# MCU.net
KiCad netlist of a schematic drawn in Altium Designer
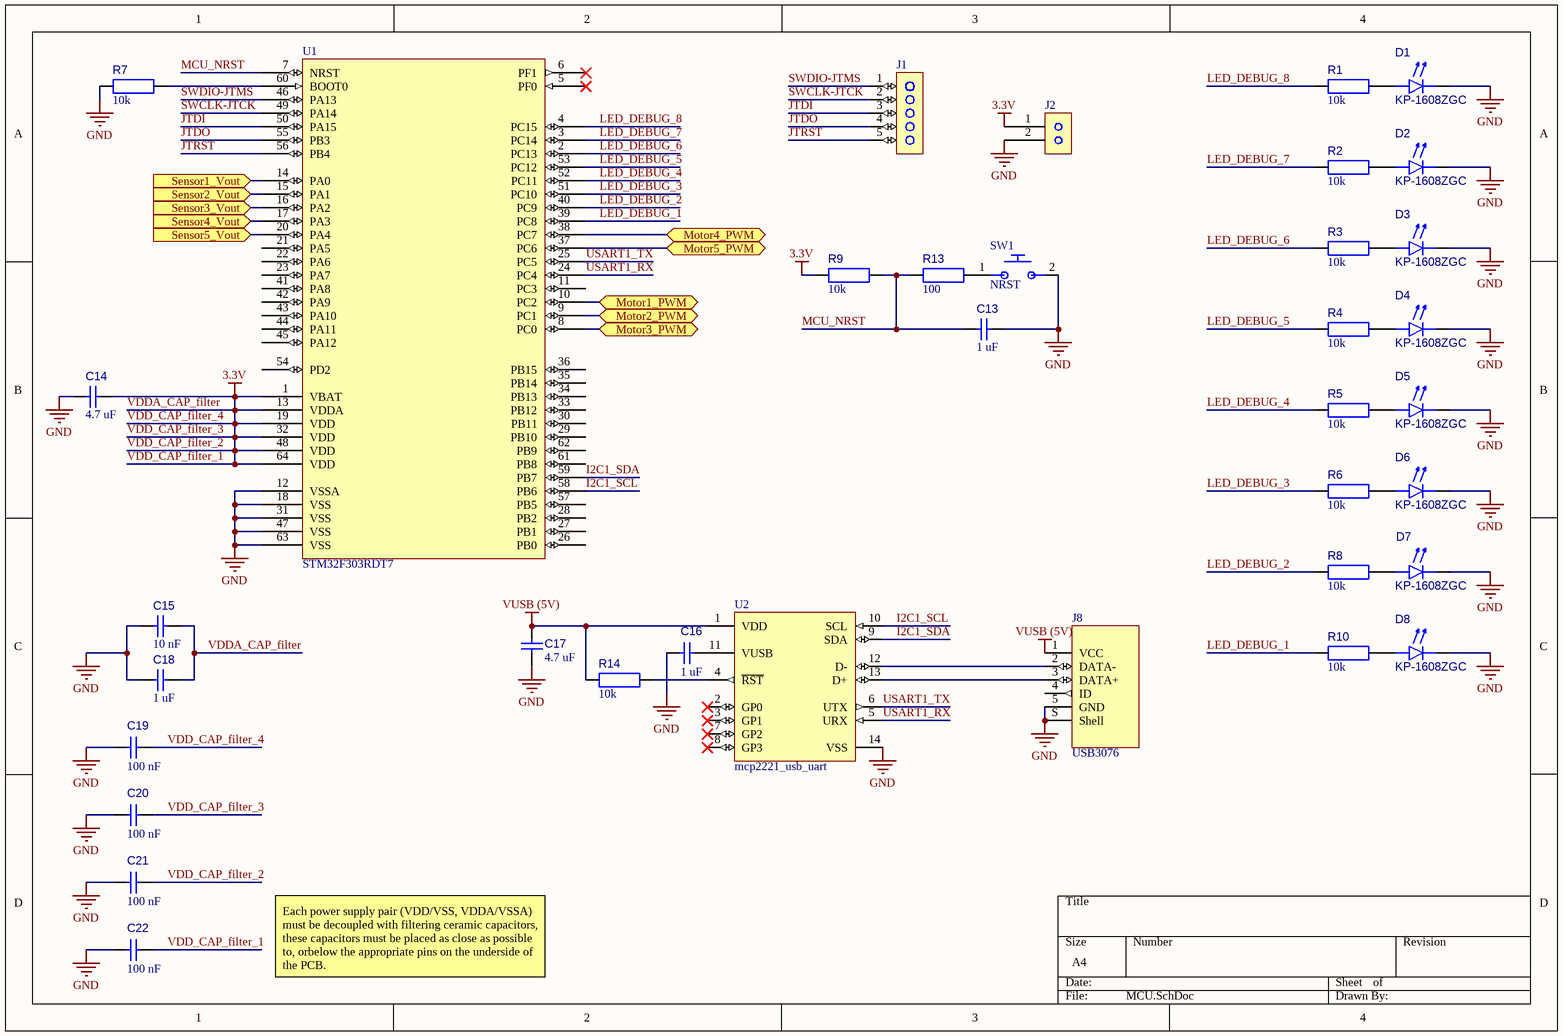
[diagram p0: MCU.SchDoc]

(export (version "E")
  (design (tool "Eeschema 10.0.6"))
  (components
    (comp (ref "C13")
      (value "Capacitor 0603 generic")
      (footprint "CAPC1608X08N")
      (description "Generic 0603 capacitor. No set voltage/capacitance rating.")
      (fields (field (name "CAPACITANCE") "1 uF"))
      (libsource (lib "Martin Kaur") (part "CAP-0603"))
    )
    (comp (ref "C14")
      (value "Capacitor 0603 generic")
      (footprint "CAPC1608X08N")
      (description "Generic 0603 capacitor. No set voltage/capacitance rating.")
      (fields (field (name "CAPACITANCE") "4.7 uF"))
      (libsource (lib "Martin Kaur") (part "CAP-0603"))
    )
    (comp (ref "C15")
      (value "Capacitor 0603 generic")
      (footprint "CAPC1608X08N")
      (description "Generic 0603 capacitor. No set voltage/capacitance rating.")
      (fields (field (name "CAPACITANCE") "10 nF"))
      (libsource (lib "Martin Kaur") (part "CAP-0603"))
    )
    (comp (ref "C16")
      (value "Capacitor 0603 generic")
      (footprint "CAPC1608X08N")
      (description "Generic 0603 capacitor. No set voltage/capacitance rating.")
      (fields (field (name "CAPACITANCE") "1 uF"))
      (libsource (lib "Martin Kaur") (part "CAP-0603"))
    )
    (comp (ref "C17")
      (value "Capacitor 0603 generic")
      (footprint "CAPC1608X08N")
      (description "Generic 0603 capacitor. No set voltage/capacitance rating.")
      (fields (field (name "CAPACITANCE") "4.7 uF"))
      (libsource (lib "Martin Kaur") (part "CAP-0603"))
    )
    (comp (ref "C18")
      (value "Capacitor 0603 generic")
      (footprint "CAPC1608X08N")
      (description "Generic 0603 capacitor. No set voltage/capacitance rating.")
      (fields (field (name "CAPACITANCE") "1 uF"))
      (libsource (lib "Martin Kaur") (part "CAP-0603"))
    )
    (comp (ref "C19")
      (value "Capacitor 0603 generic")
      (footprint "CAPC1608X08N")
      (description "Generic 0603 capacitor. No set voltage/capacitance rating.")
      (fields (field (name "CAPACITANCE") "100 nF"))
      (libsource (lib "Martin Kaur") (part "CAP-0603"))
    )
    (comp (ref "C20")
      (value "Capacitor 0603 generic")
      (footprint "CAPC1608X08N")
      (description "Generic 0603 capacitor. No set voltage/capacitance rating.")
      (fields (field (name "CAPACITANCE") "100 nF"))
      (libsource (lib "Martin Kaur") (part "CAP-0603"))
    )
    (comp (ref "C21")
      (value "Capacitor 0603 generic")
      (footprint "CAPC1608X08N")
      (description "Generic 0603 capacitor. No set voltage/capacitance rating.")
      (fields (field (name "CAPACITANCE") "100 nF"))
      (libsource (lib "Martin Kaur") (part "CAP-0603"))
    )
    (comp (ref "C22")
      (value "Capacitor 0603 generic")
      (footprint "CAPC1608X08N")
      (description "Generic 0603 capacitor. No set voltage/capacitance rating.")
      (fields (field (name "CAPACITANCE") "100 nF"))
      (libsource (lib "Martin Kaur") (part "CAP-0603"))
    )
    (comp (ref "D1")
      (value "KP-1608ZGC")
      (footprint "DIOM1608X11N")
      (description "Single Color LED, Green, Water Clear, 1.2mm")
      (libsource (lib "Martin Kaur") (part "KP-1608ZGC"))
    )
    (comp (ref "D2")
      (value "KP-1608ZGC")
      (footprint "DIOM1608X11N")
      (description "Single Color LED, Green, Water Clear, 1.2mm")
      (libsource (lib "Martin Kaur") (part "KP-1608ZGC"))
    )
    (comp (ref "D3")
      (value "KP-1608ZGC")
      (footprint "DIOM1608X11N")
      (description "Single Color LED, Green, Water Clear, 1.2mm")
      (libsource (lib "Martin Kaur") (part "KP-1608ZGC"))
    )
    (comp (ref "D4")
      (value "KP-1608ZGC")
      (footprint "DIOM1608X11N")
      (description "Single Color LED, Green, Water Clear, 1.2mm")
      (libsource (lib "Martin Kaur") (part "KP-1608ZGC"))
    )
    (comp (ref "D5")
      (value "KP-1608ZGC")
      (footprint "DIOM1608X11N")
      (description "Single Color LED, Green, Water Clear, 1.2mm")
      (libsource (lib "Martin Kaur") (part "KP-1608ZGC"))
    )
    (comp (ref "D6")
      (value "KP-1608ZGC")
      (footprint "DIOM1608X11N")
      (description "Single Color LED, Green, Water Clear, 1.2mm")
      (libsource (lib "Martin Kaur") (part "KP-1608ZGC"))
    )
    (comp (ref "D7")
      (value "KP-1608ZGC")
      (footprint "DIOM1608X11N")
      (description "Single Color LED, Green, Water Clear, 1.2mm")
      (libsource (lib "Martin Kaur") (part "KP-1608ZGC"))
    )
    (comp (ref "D8")
      (value "KP-1608ZGC")
      (footprint "DIOM1608X11N")
      (description "Single Color LED, Green, Water Clear, 1.2mm")
      (libsource (lib "Martin Kaur") (part "KP-1608ZGC"))
    )
    (comp (ref "J1")
      (value "Header-2.54-ZL201-05G")
      (footprint "Header-2.54-ZL201-05G-Footprint-1")
      (description "Male header, pitch 2.54 mm, 1x5 pins")
      (libsource (lib "Martin Kaur") (part "Header-2.54-ZL201-05G"))
    )
    (comp (ref "J2")
      (value "2_pin_f_2_54")
      (footprint "2_pin_f_2_54-Footprint-1")
      (description "2 pin female header, 2.54 mm pitch.")
      (libsource (lib "Martin Kaur") (part "2_pin_header"))
    )
    (comp (ref "J8")
      (value "USB3076")
      (footprint "USB3076-XX-X_revC")
      (libsource (lib "Martin Kaur") (part "USB3076-XX-X_revC"))
    )
    (comp (ref "R1")
      (value "Resistor 0603 generic")
      (footprint "RESC1608X04N")
      (description "Generic 0603 resistor, no fixed value.")
      (fields (field (name "RESISTANCE") "10k"))
      (libsource (lib "Martin Kaur") (part "RES0603"))
    )
    (comp (ref "R2")
      (value "Resistor 0603 generic")
      (footprint "RESC1608X04N")
      (description "Generic 0603 resistor, no fixed value.")
      (fields (field (name "RESISTANCE") "10k"))
      (libsource (lib "Martin Kaur") (part "RES0603"))
    )
    (comp (ref "R3")
      (value "Resistor 0603 generic")
      (footprint "RESC1608X04N")
      (description "Generic 0603 resistor, no fixed value.")
      (fields (field (name "RESISTANCE") "10k"))
      (libsource (lib "Martin Kaur") (part "RES0603"))
    )
    (comp (ref "R4")
      (value "Resistor 0603 generic")
      (footprint "RESC1608X04N")
      (description "Generic 0603 resistor, no fixed value.")
      (fields (field (name "RESISTANCE") "10k"))
      (libsource (lib "Martin Kaur") (part "RES0603"))
    )
    (comp (ref "R5")
      (value "Resistor 0603 generic")
      (footprint "RESC1608X04N")
      (description "Generic 0603 resistor, no fixed value.")
      (fields (field (name "RESISTANCE") "10k"))
      (libsource (lib "Martin Kaur") (part "RES0603"))
    )
    (comp (ref "R6")
      (value "Resistor 0603 generic")
      (footprint "RESC1608X04N")
      (description "Generic 0603 resistor, no fixed value.")
      (fields (field (name "RESISTANCE") "10k"))
      (libsource (lib "Martin Kaur") (part "RES0603"))
    )
    (comp (ref "R7")
      (value "Resistor 0603 generic")
      (footprint "RESC1608X04N")
      (description "Generic 0603 resistor, no fixed value.")
      (fields (field (name "RESISTANCE") "10k"))
      (libsource (lib "Martin Kaur") (part "RES0603"))
    )
    (comp (ref "R8")
      (value "Resistor 0603 generic")
      (footprint "RESC1608X04N")
      (description "Generic 0603 resistor, no fixed value.")
      (fields (field (name "RESISTANCE") "10k"))
      (libsource (lib "Martin Kaur") (part "RES0603"))
    )
    (comp (ref "R9")
      (value "Resistor 0603 generic")
      (footprint "RESC1608X04N")
      (description "Generic 0603 resistor, no fixed value.")
      (fields (field (name "RESISTANCE") "10k"))
      (libsource (lib "Martin Kaur") (part "RES0603"))
    )
    (comp (ref "R10")
      (value "Resistor 0603 generic")
      (footprint "RESC1608X04N")
      (description "Generic 0603 resistor, no fixed value.")
      (fields (field (name "RESISTANCE") "10k"))
      (libsource (lib "Martin Kaur") (part "RES0603"))
    )
    (comp (ref "R13")
      (value "Resistor 0603 generic")
      (footprint "RESC1608X04N")
      (description "Generic 0603 resistor, no fixed value.")
      (fields (field (name "RESISTANCE") "100"))
      (libsource (lib "Martin Kaur") (part "RES0603"))
    )
    (comp (ref "R14")
      (value "Resistor 0603 generic")
      (footprint "RESC1608X04N")
      (description "Generic 0603 resistor, no fixed value.")
      (fields (field (name "RESISTANCE") "10k"))
      (libsource (lib "Martin Kaur") (part "RES0603"))
    )
    (comp (ref "SW1")
      (value "NRST")
      (footprint "Button 6mm tht-Footprint-1")
      (description "Button 6mm tht")
      (libsource (lib "Martin Kaur") (part "Button"))
    )
    (comp (ref "U1")
      (value "STM32F303RDT7")
      (footprint "LQFP50P1235X1235X165-64N")
      (description "ARM Microcontroller, 32-Bit, FLASH, CORTEX-M4F CPU, 72MHz, CMOS, LQFP64")
      (libsource (lib "Martin Kaur") (part "stm32f303rdt7"))
    )
    (comp (ref "U2")
      (value "mcp2221_usb_uart")
      (footprint "FP-C04-065-SL-IPC_B")
      (description "Usb uart converter.")
      (libsource (lib "Martin Kaur") (part "USB-UART"))
    )
  )
  (nets
    (net (code "1") (name "/I2C1_SCL") (class "Default")
      (node (ref "U1") (pin "58") (pinfunction "PB6_58") (pintype "bidirectional"))
      (node (ref "U2") (pin "10") (pinfunction "SCL_10") (pintype "input"))
    )
    (net (code "2") (name "/I2C1_SDA") (class "Default")
      (node (ref "U1") (pin "59") (pinfunction "PB7_59") (pintype "bidirectional"))
      (node (ref "U2") (pin "9") (pinfunction "SDA_9") (pintype "bidirectional"))
    )
    (net (code "3") (name "/JTDI") (class "Default")
      (node (ref "J1") (pin "3") (pinfunction "3_3") (pintype "bidirectional"))
      (node (ref "U1") (pin "50") (pinfunction "PA15_50") (pintype "bidirectional"))
    )
    (net (code "4") (name "/JTDO") (class "Default")
      (node (ref "J1") (pin "4") (pinfunction "4_4") (pintype "bidirectional"))
      (node (ref "U1") (pin "55") (pinfunction "PB3_55") (pintype "bidirectional"))
    )
    (net (code "5") (name "/JTRST") (class "Default")
      (node (ref "J1") (pin "5") (pinfunction "5_5") (pintype "bidirectional"))
      (node (ref "U1") (pin "56") (pinfunction "PB4_56") (pintype "bidirectional"))
    )
    (net (code "6") (name "/LED_DEBUG_1") (class "Default")
      (node (ref "R10") (pin "1") (pinfunction "1_1") (pintype "passive"))
      (node (ref "U1") (pin "39") (pinfunction "PC8_39") (pintype "bidirectional"))
    )
    (net (code "7") (name "/LED_DEBUG_2") (class "Default")
      (node (ref "R8") (pin "1") (pinfunction "1_1") (pintype "passive"))
      (node (ref "U1") (pin "40") (pinfunction "PC9_40") (pintype "bidirectional"))
    )
    (net (code "8") (name "/LED_DEBUG_3") (class "Default")
      (node (ref "R6") (pin "1") (pinfunction "1_1") (pintype "passive"))
      (node (ref "U1") (pin "51") (pinfunction "PC10_51") (pintype "bidirectional"))
    )
    (net (code "9") (name "/LED_DEBUG_4") (class "Default")
      (node (ref "R5") (pin "1") (pinfunction "1_1") (pintype "passive"))
      (node (ref "U1") (pin "52") (pinfunction "PC11_52") (pintype "bidirectional"))
    )
    (net (code "10") (name "/LED_DEBUG_5") (class "Default")
      (node (ref "R4") (pin "1") (pinfunction "1_1") (pintype "passive"))
      (node (ref "U1") (pin "53") (pinfunction "PC12_53") (pintype "bidirectional"))
    )
    (net (code "11") (name "/LED_DEBUG_6") (class "Default")
      (node (ref "R3") (pin "1") (pinfunction "1_1") (pintype "passive"))
      (node (ref "U1") (pin "2") (pinfunction "PC13_2") (pintype "bidirectional"))
    )
    (net (code "12") (name "/LED_DEBUG_7") (class "Default")
      (node (ref "R2") (pin "1") (pinfunction "1_1") (pintype "passive"))
      (node (ref "U1") (pin "3") (pinfunction "PC14_3") (pintype "bidirectional"))
    )
    (net (code "13") (name "/LED_DEBUG_8") (class "Default")
      (node (ref "R1") (pin "1") (pinfunction "1_1") (pintype "passive"))
      (node (ref "U1") (pin "4") (pinfunction "PC15_4") (pintype "bidirectional"))
    )
    (net (code "14") (name "/MCU_NRST") (class "Default")
      (node (ref "C13") (pin "2") (pinfunction "2_2") (pintype "passive"))
      (node (ref "R13") (pin "1") (pinfunction "1_1") (pintype "passive"))
      (node (ref "R9") (pin "2") (pinfunction "2_2") (pintype "passive"))
      (node (ref "U1") (pin "7") (pinfunction "NRST_7") (pintype "bidirectional"))
    )
    (net (code "15") (name "/Motor1_PWM") (class "Default")
      (node (ref "U1") (pin "10") (pinfunction "PC2_10") (pintype "bidirectional"))
    )
    (net (code "16") (name "/Motor2_PWM") (class "Default")
      (node (ref "U1") (pin "9") (pinfunction "PC1_9") (pintype "bidirectional"))
    )
    (net (code "17") (name "/Motor3_PWM") (class "Default")
      (node (ref "U1") (pin "8") (pinfunction "PC0_8") (pintype "bidirectional"))
    )
    (net (code "18") (name "/Motor4_PWM") (class "Default")
      (node (ref "U1") (pin "38") (pinfunction "PC7_38") (pintype "bidirectional"))
    )
    (net (code "19") (name "/Motor5_PWM") (class "Default")
      (node (ref "U1") (pin "37") (pinfunction "PC6_37") (pintype "bidirectional"))
    )
    (net (code "20") (name "/SWCLK-JTCK") (class "Default")
      (node (ref "J1") (pin "2") (pinfunction "2_2") (pintype "bidirectional"))
      (node (ref "U1") (pin "49") (pinfunction "PA14_49") (pintype "bidirectional"))
    )
    (net (code "21") (name "/SWDIO-JTMS") (class "Default")
      (node (ref "J1") (pin "1") (pinfunction "1_1") (pintype "bidirectional"))
      (node (ref "U1") (pin "46") (pinfunction "PA13_46") (pintype "bidirectional"))
    )
    (net (code "22") (name "/Sensor1_Vout") (class "Default")
      (node (ref "U1") (pin "14") (pinfunction "PA0_14") (pintype "bidirectional"))
    )
    (net (code "23") (name "/Sensor2_Vout") (class "Default")
      (node (ref "U1") (pin "15") (pinfunction "PA1_15") (pintype "bidirectional"))
    )
    (net (code "24") (name "/Sensor3_Vout") (class "Default")
      (node (ref "U1") (pin "16") (pinfunction "PA2_16") (pintype "bidirectional"))
    )
    (net (code "25") (name "/Sensor4_Vout") (class "Default")
      (node (ref "U1") (pin "17") (pinfunction "PA3_17") (pintype "bidirectional"))
    )
    (net (code "26") (name "/Sensor5_Vout") (class "Default")
      (node (ref "U1") (pin "20") (pinfunction "PA4_20") (pintype "bidirectional"))
    )
    (net (code "27") (name "/USART1_RX") (class "Default")
      (node (ref "U1") (pin "24") (pinfunction "PC4_24") (pintype "bidirectional"))
      (node (ref "U2") (pin "5") (pinfunction "URX_5") (pintype "input"))
    )
    (net (code "28") (name "/USART1_TX") (class "Default")
      (node (ref "U1") (pin "25") (pinfunction "PC5_25") (pintype "bidirectional"))
      (node (ref "U2") (pin "6") (pinfunction "UTX_6") (pintype "output"))
    )
    (net (code "29") (name "3.3V") (class "Default")
      (node (ref "C14") (pin "1") (pinfunction "1_1") (pintype "passive"))
      (node (ref "C15") (pin "1") (pinfunction "1_1") (pintype "passive"))
      (node (ref "C18") (pin "1") (pinfunction "1_1") (pintype "passive"))
      (node (ref "C19") (pin "1") (pinfunction "1_1") (pintype "passive"))
      (node (ref "C20") (pin "1") (pinfunction "1_1") (pintype "passive"))
      (node (ref "C21") (pin "1") (pinfunction "1_1") (pintype "passive"))
      (node (ref "C22") (pin "1") (pinfunction "1_1") (pintype "passive"))
      (node (ref "J2") (pin "1") (pinfunction "VDD_1") (pintype "power_in"))
      (node (ref "R9") (pin "1") (pinfunction "1_1") (pintype "passive"))
      (node (ref "U1") (pin "1") (pinfunction "VBAT_1") (pintype "power_in"))
      (node (ref "U1") (pin "13") (pinfunction "VDDA_13") (pintype "power_in"))
      (node (ref "U1") (pin "19") (pinfunction "VDD_19") (pintype "power_in"))
      (node (ref "U1") (pin "32") (pinfunction "VDD_32") (pintype "power_in"))
      (node (ref "U1") (pin "48") (pinfunction "VDD_48") (pintype "power_in"))
      (node (ref "U1") (pin "64") (pinfunction "VDD_64") (pintype "power_in"))
    )
    (net (code "30") (name "GND") (class "Default")
      (node (ref "C13") (pin "1") (pinfunction "1_1") (pintype "passive"))
      (node (ref "C14") (pin "2") (pinfunction "2_2") (pintype "passive"))
      (node (ref "C15") (pin "2") (pinfunction "2_2") (pintype "passive"))
      (node (ref "C16") (pin "2") (pinfunction "2_2") (pintype "passive"))
      (node (ref "C17") (pin "2") (pinfunction "2_2") (pintype "passive"))
      (node (ref "C18") (pin "2") (pinfunction "2_2") (pintype "passive"))
      (node (ref "C19") (pin "2") (pinfunction "2_2") (pintype "passive"))
      (node (ref "C20") (pin "2") (pinfunction "2_2") (pintype "passive"))
      (node (ref "C21") (pin "2") (pinfunction "2_2") (pintype "passive"))
      (node (ref "C22") (pin "2") (pinfunction "2_2") (pintype "passive"))
      (node (ref "D1") (pin "1") (pinfunction "-_1") (pintype "passive"))
      (node (ref "D2") (pin "1") (pinfunction "-_1") (pintype "passive"))
      (node (ref "D3") (pin "1") (pinfunction "-_1") (pintype "passive"))
      (node (ref "D4") (pin "1") (pinfunction "-_1") (pintype "passive"))
      (node (ref "D5") (pin "1") (pinfunction "-_1") (pintype "passive"))
      (node (ref "D6") (pin "1") (pinfunction "-_1") (pintype "passive"))
      (node (ref "D7") (pin "1") (pinfunction "-_1") (pintype "passive"))
      (node (ref "D8") (pin "1") (pinfunction "-_1") (pintype "passive"))
      (node (ref "J2") (pin "2") (pinfunction "GND_2") (pintype "power_in"))
      (node (ref "J8") (pin "5") (pinfunction "GND_5") (pintype "power_in"))
      (node (ref "J8") (pin "S") (pinfunction "Shell_S") (pintype "power_in"))
      (node (ref "R7") (pin "1") (pinfunction "1_1") (pintype "passive"))
      (node (ref "SW1") (pin "2") (pinfunction "2_2") (pintype "passive"))
      (node (ref "U1") (pin "12") (pinfunction "VSSA_12") (pintype "power_in"))
      (node (ref "U1") (pin "18") (pinfunction "VSS_18") (pintype "power_in"))
      (node (ref "U1") (pin "31") (pinfunction "VSS_31") (pintype "power_in"))
      (node (ref "U1") (pin "47") (pinfunction "VSS_47") (pintype "power_in"))
      (node (ref "U1") (pin "63") (pinfunction "VSS_63") (pintype "power_in"))
      (node (ref "U2") (pin "14") (pinfunction "VSS_14") (pintype "power_in"))
    )
    (net (code "31") (name "Net-(D1-+)") (class "Default")
      (node (ref "D1") (pin "2") (pinfunction "+_2") (pintype "passive"))
      (node (ref "R1") (pin "2") (pinfunction "2_2") (pintype "passive"))
    )
    (net (code "32") (name "Net-(D2-+)") (class "Default")
      (node (ref "D2") (pin "2") (pinfunction "+_2") (pintype "passive"))
      (node (ref "R2") (pin "2") (pinfunction "2_2") (pintype "passive"))
    )
    (net (code "33") (name "Net-(D3-+)") (class "Default")
      (node (ref "D3") (pin "2") (pinfunction "+_2") (pintype "passive"))
      (node (ref "R3") (pin "2") (pinfunction "2_2") (pintype "passive"))
    )
    (net (code "34") (name "Net-(D4-+)") (class "Default")
      (node (ref "D4") (pin "2") (pinfunction "+_2") (pintype "passive"))
      (node (ref "R4") (pin "2") (pinfunction "2_2") (pintype "passive"))
    )
    (net (code "35") (name "Net-(D5-+)") (class "Default")
      (node (ref "D5") (pin "2") (pinfunction "+_2") (pintype "passive"))
      (node (ref "R5") (pin "2") (pinfunction "2_2") (pintype "passive"))
    )
    (net (code "36") (name "Net-(D6-+)") (class "Default")
      (node (ref "D6") (pin "2") (pinfunction "+_2") (pintype "passive"))
      (node (ref "R6") (pin "2") (pinfunction "2_2") (pintype "passive"))
    )
    (net (code "37") (name "Net-(D7-+)") (class "Default")
      (node (ref "D7") (pin "2") (pinfunction "+_2") (pintype "passive"))
      (node (ref "R8") (pin "2") (pinfunction "2_2") (pintype "passive"))
    )
    (net (code "38") (name "Net-(D8-+)") (class "Default")
      (node (ref "D8") (pin "2") (pinfunction "+_2") (pintype "passive"))
      (node (ref "R10") (pin "2") (pinfunction "2_2") (pintype "passive"))
    )
    (net (code "39") (name "Net-(J8-DATA+)") (class "Default")
      (node (ref "J8") (pin "3") (pinfunction "DATA+_3") (pintype "bidirectional"))
      (node (ref "U2") (pin "13") (pinfunction "D+_13") (pintype "bidirectional"))
    )
    (net (code "40") (name "Net-(J8-DATA-)") (class "Default")
      (node (ref "J8") (pin "2") (pinfunction "DATA-_2") (pintype "bidirectional"))
      (node (ref "U2") (pin "12") (pinfunction "D-_12") (pintype "bidirectional"))
    )
    (net (code "41") (name "Net-(R13-Pad2)") (class "Default")
      (node (ref "R13") (pin "2") (pinfunction "2_2") (pintype "passive"))
      (node (ref "SW1") (pin "1") (pinfunction "1_1") (pintype "passive"))
    )
    (net (code "42") (name "Net-(U1-BOOT0)") (class "Default")
      (node (ref "R7") (pin "2") (pinfunction "2_2") (pintype "passive"))
      (node (ref "U1") (pin "60") (pinfunction "BOOT0_60") (pintype "input"))
    )
    (net (code "43") (name "Net-(U2-VUSB)") (class "Default")
      (node (ref "C16") (pin "1") (pinfunction "1_1") (pintype "passive"))
      (node (ref "U2") (pin "11") (pinfunction "VUSB_11") (pintype "power_in"))
    )
    (net (code "44") (name "Net-(U2-~{RST})") (class "Default")
      (node (ref "R14") (pin "1") (pinfunction "1_1") (pintype "passive"))
      (node (ref "U2") (pin "4") (pinfunction "~{RST}_4") (pintype "output"))
    )
    (net (code "45") (name "VUSB (5V)") (class "Default")
      (node (ref "C17") (pin "1") (pinfunction "1_1") (pintype "passive"))
      (node (ref "J8") (pin "1") (pinfunction "VCC_1") (pintype "power_in"))
      (node (ref "R14") (pin "2") (pinfunction "2_2") (pintype "passive"))
      (node (ref "U2") (pin "1") (pinfunction "VDD_1") (pintype "power_in"))
    )
    (net (code "46") (name "unconnected-(J8-ID-Pad4)") (class "Default")
      (node (ref "J8") (pin "4") (pinfunction "ID_4") (pintype "output"))
    )
    (net (code "47") (name "unconnected-(U1-PA5-Pad21)") (class "Default")
      (node (ref "U1") (pin "21") (pinfunction "PA5_21") (pintype "bidirectional"))
    )
    (net (code "48") (name "unconnected-(U1-PA6-Pad22)") (class "Default")
      (node (ref "U1") (pin "22") (pinfunction "PA6_22") (pintype "bidirectional"))
    )
    (net (code "49") (name "unconnected-(U1-PA7-Pad23)") (class "Default")
      (node (ref "U1") (pin "23") (pinfunction "PA7_23") (pintype "bidirectional"))
    )
    (net (code "50") (name "unconnected-(U1-PA8-Pad41)") (class "Default")
      (node (ref "U1") (pin "41") (pinfunction "PA8_41") (pintype "bidirectional"))
    )
    (net (code "51") (name "unconnected-(U1-PA9-Pad42)") (class "Default")
      (node (ref "U1") (pin "42") (pinfunction "PA9_42") (pintype "bidirectional"))
    )
    (net (code "52") (name "unconnected-(U1-PA10-Pad43)") (class "Default")
      (node (ref "U1") (pin "43") (pinfunction "PA10_43") (pintype "bidirectional"))
    )
    (net (code "53") (name "unconnected-(U1-PA11-Pad44)") (class "Default")
      (node (ref "U1") (pin "44") (pinfunction "PA11_44") (pintype "bidirectional"))
    )
    (net (code "54") (name "unconnected-(U1-PA12-Pad45)") (class "Default")
      (node (ref "U1") (pin "45") (pinfunction "PA12_45") (pintype "bidirectional"))
    )
    (net (code "55") (name "unconnected-(U1-PB0-Pad26)") (class "Default")
      (node (ref "U1") (pin "26") (pinfunction "PB0_26") (pintype "bidirectional"))
    )
    (net (code "56") (name "unconnected-(U1-PB1-Pad27)") (class "Default")
      (node (ref "U1") (pin "27") (pinfunction "PB1_27") (pintype "bidirectional"))
    )
    (net (code "57") (name "unconnected-(U1-PB2-Pad28)") (class "Default")
      (node (ref "U1") (pin "28") (pinfunction "PB2_28") (pintype "bidirectional"))
    )
    (net (code "58") (name "unconnected-(U1-PB5-Pad57)") (class "Default")
      (node (ref "U1") (pin "57") (pinfunction "PB5_57") (pintype "bidirectional"))
    )
    (net (code "59") (name "unconnected-(U1-PB8-Pad61)") (class "Default")
      (node (ref "U1") (pin "61") (pinfunction "PB8_61") (pintype "bidirectional"))
    )
    (net (code "60") (name "unconnected-(U1-PB9-Pad62)") (class "Default")
      (node (ref "U1") (pin "62") (pinfunction "PB9_62") (pintype "bidirectional"))
    )
    (net (code "61") (name "unconnected-(U1-PB10-Pad29)") (class "Default")
      (node (ref "U1") (pin "29") (pinfunction "PB10_29") (pintype "bidirectional"))
    )
    (net (code "62") (name "unconnected-(U1-PB11-Pad30)") (class "Default")
      (node (ref "U1") (pin "30") (pinfunction "PB11_30") (pintype "bidirectional"))
    )
    (net (code "63") (name "unconnected-(U1-PB12-Pad33)") (class "Default")
      (node (ref "U1") (pin "33") (pinfunction "PB12_33") (pintype "bidirectional"))
    )
    (net (code "64") (name "unconnected-(U1-PB13-Pad34)") (class "Default")
      (node (ref "U1") (pin "34") (pinfunction "PB13_34") (pintype "bidirectional"))
    )
    (net (code "65") (name "unconnected-(U1-PB14-Pad35)") (class "Default")
      (node (ref "U1") (pin "35") (pinfunction "PB14_35") (pintype "bidirectional"))
    )
    (net (code "66") (name "unconnected-(U1-PB15-Pad36)") (class "Default")
      (node (ref "U1") (pin "36") (pinfunction "PB15_36") (pintype "bidirectional"))
    )
    (net (code "67") (name "unconnected-(U1-PC3-Pad11)") (class "Default")
      (node (ref "U1") (pin "11") (pinfunction "PC3_11") (pintype "bidirectional"))
    )
    (net (code "68") (name "unconnected-(U1-PD2-Pad54)") (class "Default")
      (node (ref "U1") (pin "54") (pinfunction "PD2_54") (pintype "bidirectional"))
    )
    (net (code "69") (name "unconnected-(U1-PF0-Pad5)") (class "Default")
      (node (ref "U1") (pin "5") (pinfunction "PF0_5") (pintype "input+no_connect"))
    )
    (net (code "70") (name "unconnected-(U1-PF1-Pad6)") (class "Default")
      (node (ref "U1") (pin "6") (pinfunction "PF1_6") (pintype "output+no_connect"))
    )
    (net (code "71") (name "unconnected-(U2-GP0-Pad2)") (class "Default")
      (node (ref "U2") (pin "2") (pinfunction "GP0_2") (pintype "bidirectional+no_connect"))
    )
    (net (code "72") (name "unconnected-(U2-GP1-Pad3)") (class "Default")
      (node (ref "U2") (pin "3") (pinfunction "GP1_3") (pintype "bidirectional+no_connect"))
    )
    (net (code "73") (name "unconnected-(U2-GP2-Pad7)") (class "Default")
      (node (ref "U2") (pin "7") (pinfunction "GP2_7") (pintype "bidirectional+no_connect"))
    )
    (net (code "74") (name "unconnected-(U2-GP3-Pad8)") (class "Default")
      (node (ref "U2") (pin "8") (pinfunction "GP3_8") (pintype "bidirectional+no_connect"))
    )
  )
)
